# linebot.net
KiCad netlist of a schematic drawn in EAGLE
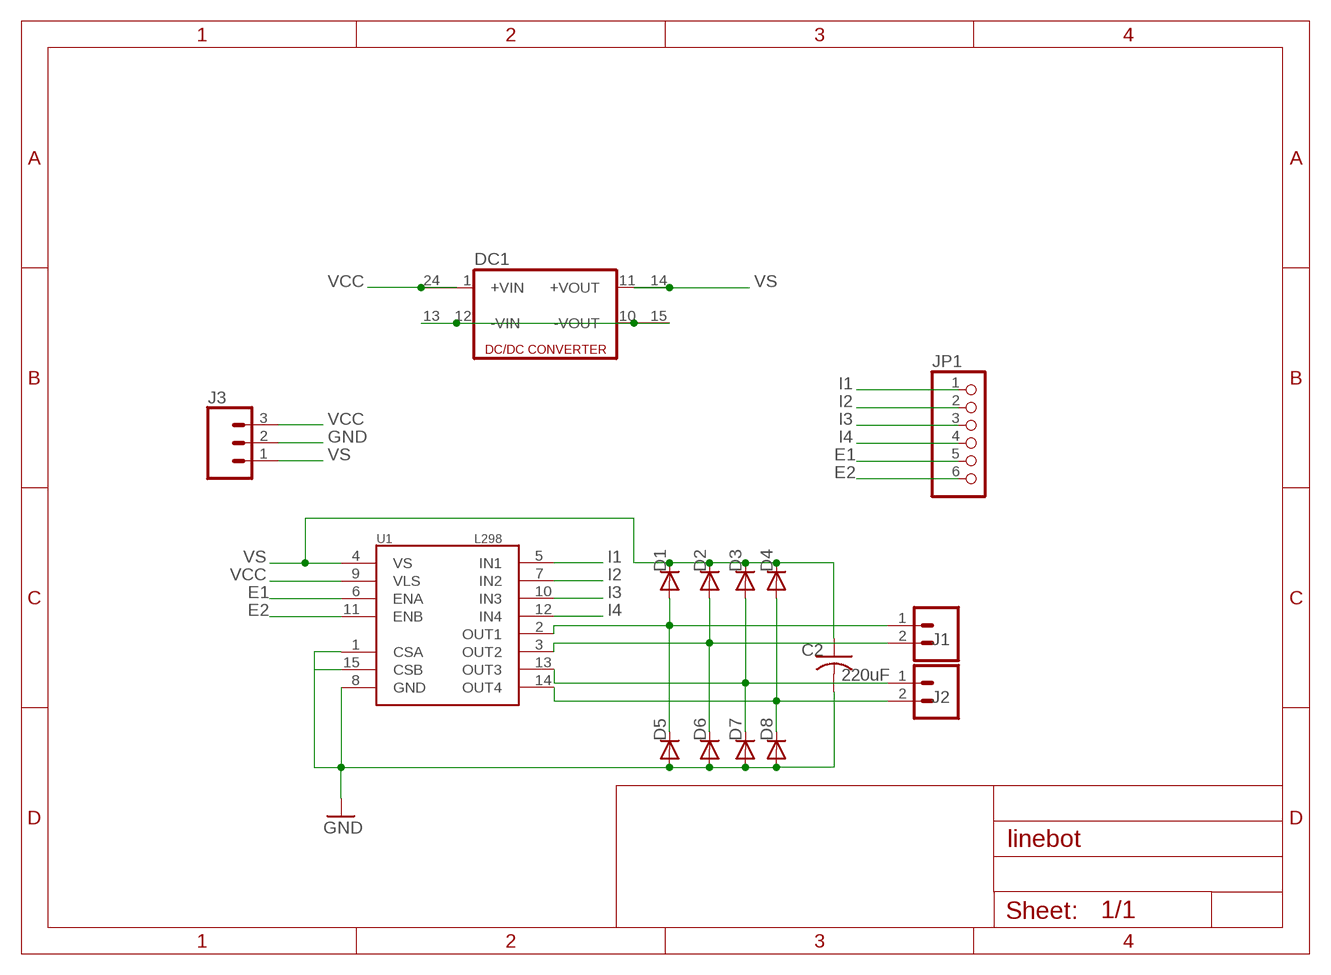
[diagram p0: schematic, sheet 1]

(export (version "E")
  (design (tool "Eeschema 10.0.6"))
  (components
    (comp (ref "C2")
      (value "220uF")
      (footprint "eagle-import:C025-024X044")
      (libsource (lib "eagle-import") (part "C-US025-024X044"))
    )
    (comp (ref "D1")
      (value "1N4004")
      (footprint "eagle-import:DO41-10")
      (libsource (lib "eagle-import") (part "1N4004"))
    )
    (comp (ref "D2")
      (value "1N4004")
      (footprint "eagle-import:DO41-10")
      (libsource (lib "eagle-import") (part "1N4004"))
    )
    (comp (ref "D3")
      (value "1N4004")
      (footprint "eagle-import:DO41-10")
      (libsource (lib "eagle-import") (part "1N4004"))
    )
    (comp (ref "D4")
      (value "1N4004")
      (footprint "eagle-import:DO41-10")
      (libsource (lib "eagle-import") (part "1N4004"))
    )
    (comp (ref "D5")
      (value "1N4004")
      (footprint "eagle-import:DO41-10")
      (libsource (lib "eagle-import") (part "1N4004"))
    )
    (comp (ref "D6")
      (value "1N4004")
      (footprint "eagle-import:DO41-10")
      (libsource (lib "eagle-import") (part "1N4004"))
    )
    (comp (ref "D7")
      (value "1N4004")
      (footprint "eagle-import:DO41-10")
      (libsource (lib "eagle-import") (part "1N4004"))
    )
    (comp (ref "D8")
      (value "1N4004")
      (footprint "eagle-import:DO41-10")
      (libsource (lib "eagle-import") (part "1N4004"))
    )
    (comp (ref "DC1")
      (value "DC213R")
      (footprint "eagle-import:CMK")
      (libsource (lib "eagle-import") (part "DC213R"))
    )
    (comp (ref "J1")
      (value "CONN_02")
      (footprint "eagle-import:1X02")
      (libsource (lib "eagle-import") (part "CONN_02"))
    )
    (comp (ref "J2")
      (value "CONN_02")
      (footprint "eagle-import:1X02")
      (libsource (lib "eagle-import") (part "CONN_02"))
    )
    (comp (ref "J3")
      (value "455-1750-1-ND")
      (footprint "eagle-import:1X03")
      (libsource (lib "eagle-import") (part "CONN_03"))
    )
    (comp (ref "JP1")
      (value "PINHD-1X6")
      (footprint "eagle-import:1X06")
      (libsource (lib "eagle-import") (part "PINHD-1X6"))
    )
    (comp (ref "U1")
      (value "L298")
      (footprint "eagle-import:MULTIWATT15")
      (libsource (lib "eagle-import") (part "L298"))
    )
  )
  (nets
    (net (code "1") (name "/E1") (class "Default")
      (node (ref "JP1") (pin "5") (pinfunction "5_5") (pintype "passive"))
      (node (ref "U1") (pin "6") (pinfunction "ENA_6") (pintype "bidirectional"))
    )
    (net (code "2") (name "/E2") (class "Default")
      (node (ref "JP1") (pin "6") (pinfunction "6_6") (pintype "passive"))
      (node (ref "U1") (pin "11") (pinfunction "ENB_11") (pintype "bidirectional"))
    )
    (net (code "3") (name "/I1") (class "Default")
      (node (ref "JP1") (pin "1") (pinfunction "1_1") (pintype "passive"))
      (node (ref "U1") (pin "5") (pinfunction "IN1_5") (pintype "bidirectional"))
    )
    (net (code "4") (name "/I2") (class "Default")
      (node (ref "JP1") (pin "2") (pinfunction "2_2") (pintype "passive"))
      (node (ref "U1") (pin "7") (pinfunction "IN2_7") (pintype "bidirectional"))
    )
    (net (code "5") (name "/I3") (class "Default")
      (node (ref "JP1") (pin "3") (pinfunction "3_3") (pintype "passive"))
      (node (ref "U1") (pin "10") (pinfunction "IN3_10") (pintype "bidirectional"))
    )
    (net (code "6") (name "/I4") (class "Default")
      (node (ref "JP1") (pin "4") (pinfunction "4_4") (pintype "passive"))
      (node (ref "U1") (pin "12") (pinfunction "IN4_12") (pintype "bidirectional"))
    )
    (net (code "7") (name "/VCC") (class "Default")
      (node (ref "DC1") (pin "1") (pinfunction "+VIN_1") (pintype "passive"))
      (node (ref "DC1") (pin "24") (pinfunction "+VIN1_24") (pintype "passive"))
      (node (ref "J3") (pin "3") (pinfunction "3_3") (pintype "passive"))
      (node (ref "U1") (pin "9") (pinfunction "VLS_9") (pintype "bidirectional"))
    )
    (net (code "8") (name "/VS") (class "Default")
      (node (ref "C2") (pin "1") (pinfunction "1_1") (pintype "passive"))
      (node (ref "D1") (pin "C") (pinfunction "C_C") (pintype "passive"))
      (node (ref "D2") (pin "C") (pinfunction "C_C") (pintype "passive"))
      (node (ref "D3") (pin "C") (pinfunction "C_C") (pintype "passive"))
      (node (ref "D4") (pin "C") (pinfunction "C_C") (pintype "passive"))
      (node (ref "DC1") (pin "11") (pinfunction "+VOUT_11") (pintype "passive"))
      (node (ref "DC1") (pin "14") (pinfunction "+VOUT1_14") (pintype "passive"))
      (node (ref "J3") (pin "1") (pinfunction "1_1") (pintype "passive"))
      (node (ref "U1") (pin "4") (pinfunction "VS_4") (pintype "bidirectional"))
    )
    (net (code "9") (name "GND") (class "Default")
      (node (ref "C2") (pin "2") (pinfunction "2_2") (pintype "passive"))
      (node (ref "D5") (pin "A") (pinfunction "A_A") (pintype "passive"))
      (node (ref "D6") (pin "A") (pinfunction "A_A") (pintype "passive"))
      (node (ref "D7") (pin "A") (pinfunction "A_A") (pintype "passive"))
      (node (ref "D8") (pin "A") (pinfunction "A_A") (pintype "passive"))
      (node (ref "J3") (pin "2") (pinfunction "2_2") (pintype "passive"))
      (node (ref "U1") (pin "1") (pinfunction "CSA_1") (pintype "bidirectional"))
      (node (ref "U1") (pin "15") (pinfunction "CSB_15") (pintype "bidirectional"))
      (node (ref "U1") (pin "8") (pinfunction "GND_8") (pintype "bidirectional"))
    )
    (net (code "10") (name "Net-(DC1--VIN)") (class "Default")
      (node (ref "DC1") (pin "10") (pinfunction "-VOUT_10") (pintype "passive"))
      (node (ref "DC1") (pin "12") (pinfunction "-VIN_12") (pintype "passive"))
      (node (ref "DC1") (pin "13") (pinfunction "-VIN1_13") (pintype "passive"))
      (node (ref "DC1") (pin "15") (pinfunction "-VOUT1_15") (pintype "passive"))
    )
    (net (code "11") (name "Net-(U1-OUT1)") (class "Default")
      (node (ref "D1") (pin "A") (pinfunction "A_A") (pintype "passive"))
      (node (ref "D5") (pin "C") (pinfunction "C_C") (pintype "passive"))
      (node (ref "J1") (pin "1") (pinfunction "1_1") (pintype "passive"))
      (node (ref "U1") (pin "2") (pinfunction "OUT1_2") (pintype "bidirectional"))
    )
    (net (code "12") (name "Net-(U1-OUT2)") (class "Default")
      (node (ref "D2") (pin "A") (pinfunction "A_A") (pintype "passive"))
      (node (ref "D6") (pin "C") (pinfunction "C_C") (pintype "passive"))
      (node (ref "J1") (pin "2") (pinfunction "2_2") (pintype "passive"))
      (node (ref "U1") (pin "3") (pinfunction "OUT2_3") (pintype "bidirectional"))
    )
    (net (code "13") (name "Net-(U1-OUT3)") (class "Default")
      (node (ref "D3") (pin "A") (pinfunction "A_A") (pintype "passive"))
      (node (ref "D7") (pin "C") (pinfunction "C_C") (pintype "passive"))
      (node (ref "J2") (pin "1") (pinfunction "1_1") (pintype "passive"))
      (node (ref "U1") (pin "13") (pinfunction "OUT3_13") (pintype "bidirectional"))
    )
    (net (code "14") (name "Net-(U1-OUT4)") (class "Default")
      (node (ref "D4") (pin "A") (pinfunction "A_A") (pintype "passive"))
      (node (ref "D8") (pin "C") (pinfunction "C_C") (pintype "passive"))
      (node (ref "J2") (pin "2") (pinfunction "2_2") (pintype "passive"))
      (node (ref "U1") (pin "14") (pinfunction "OUT4_14") (pintype "bidirectional"))
    )
  )
)
